# design.net
KiCad netlist of a schematic drawn in EasyEDA Pro
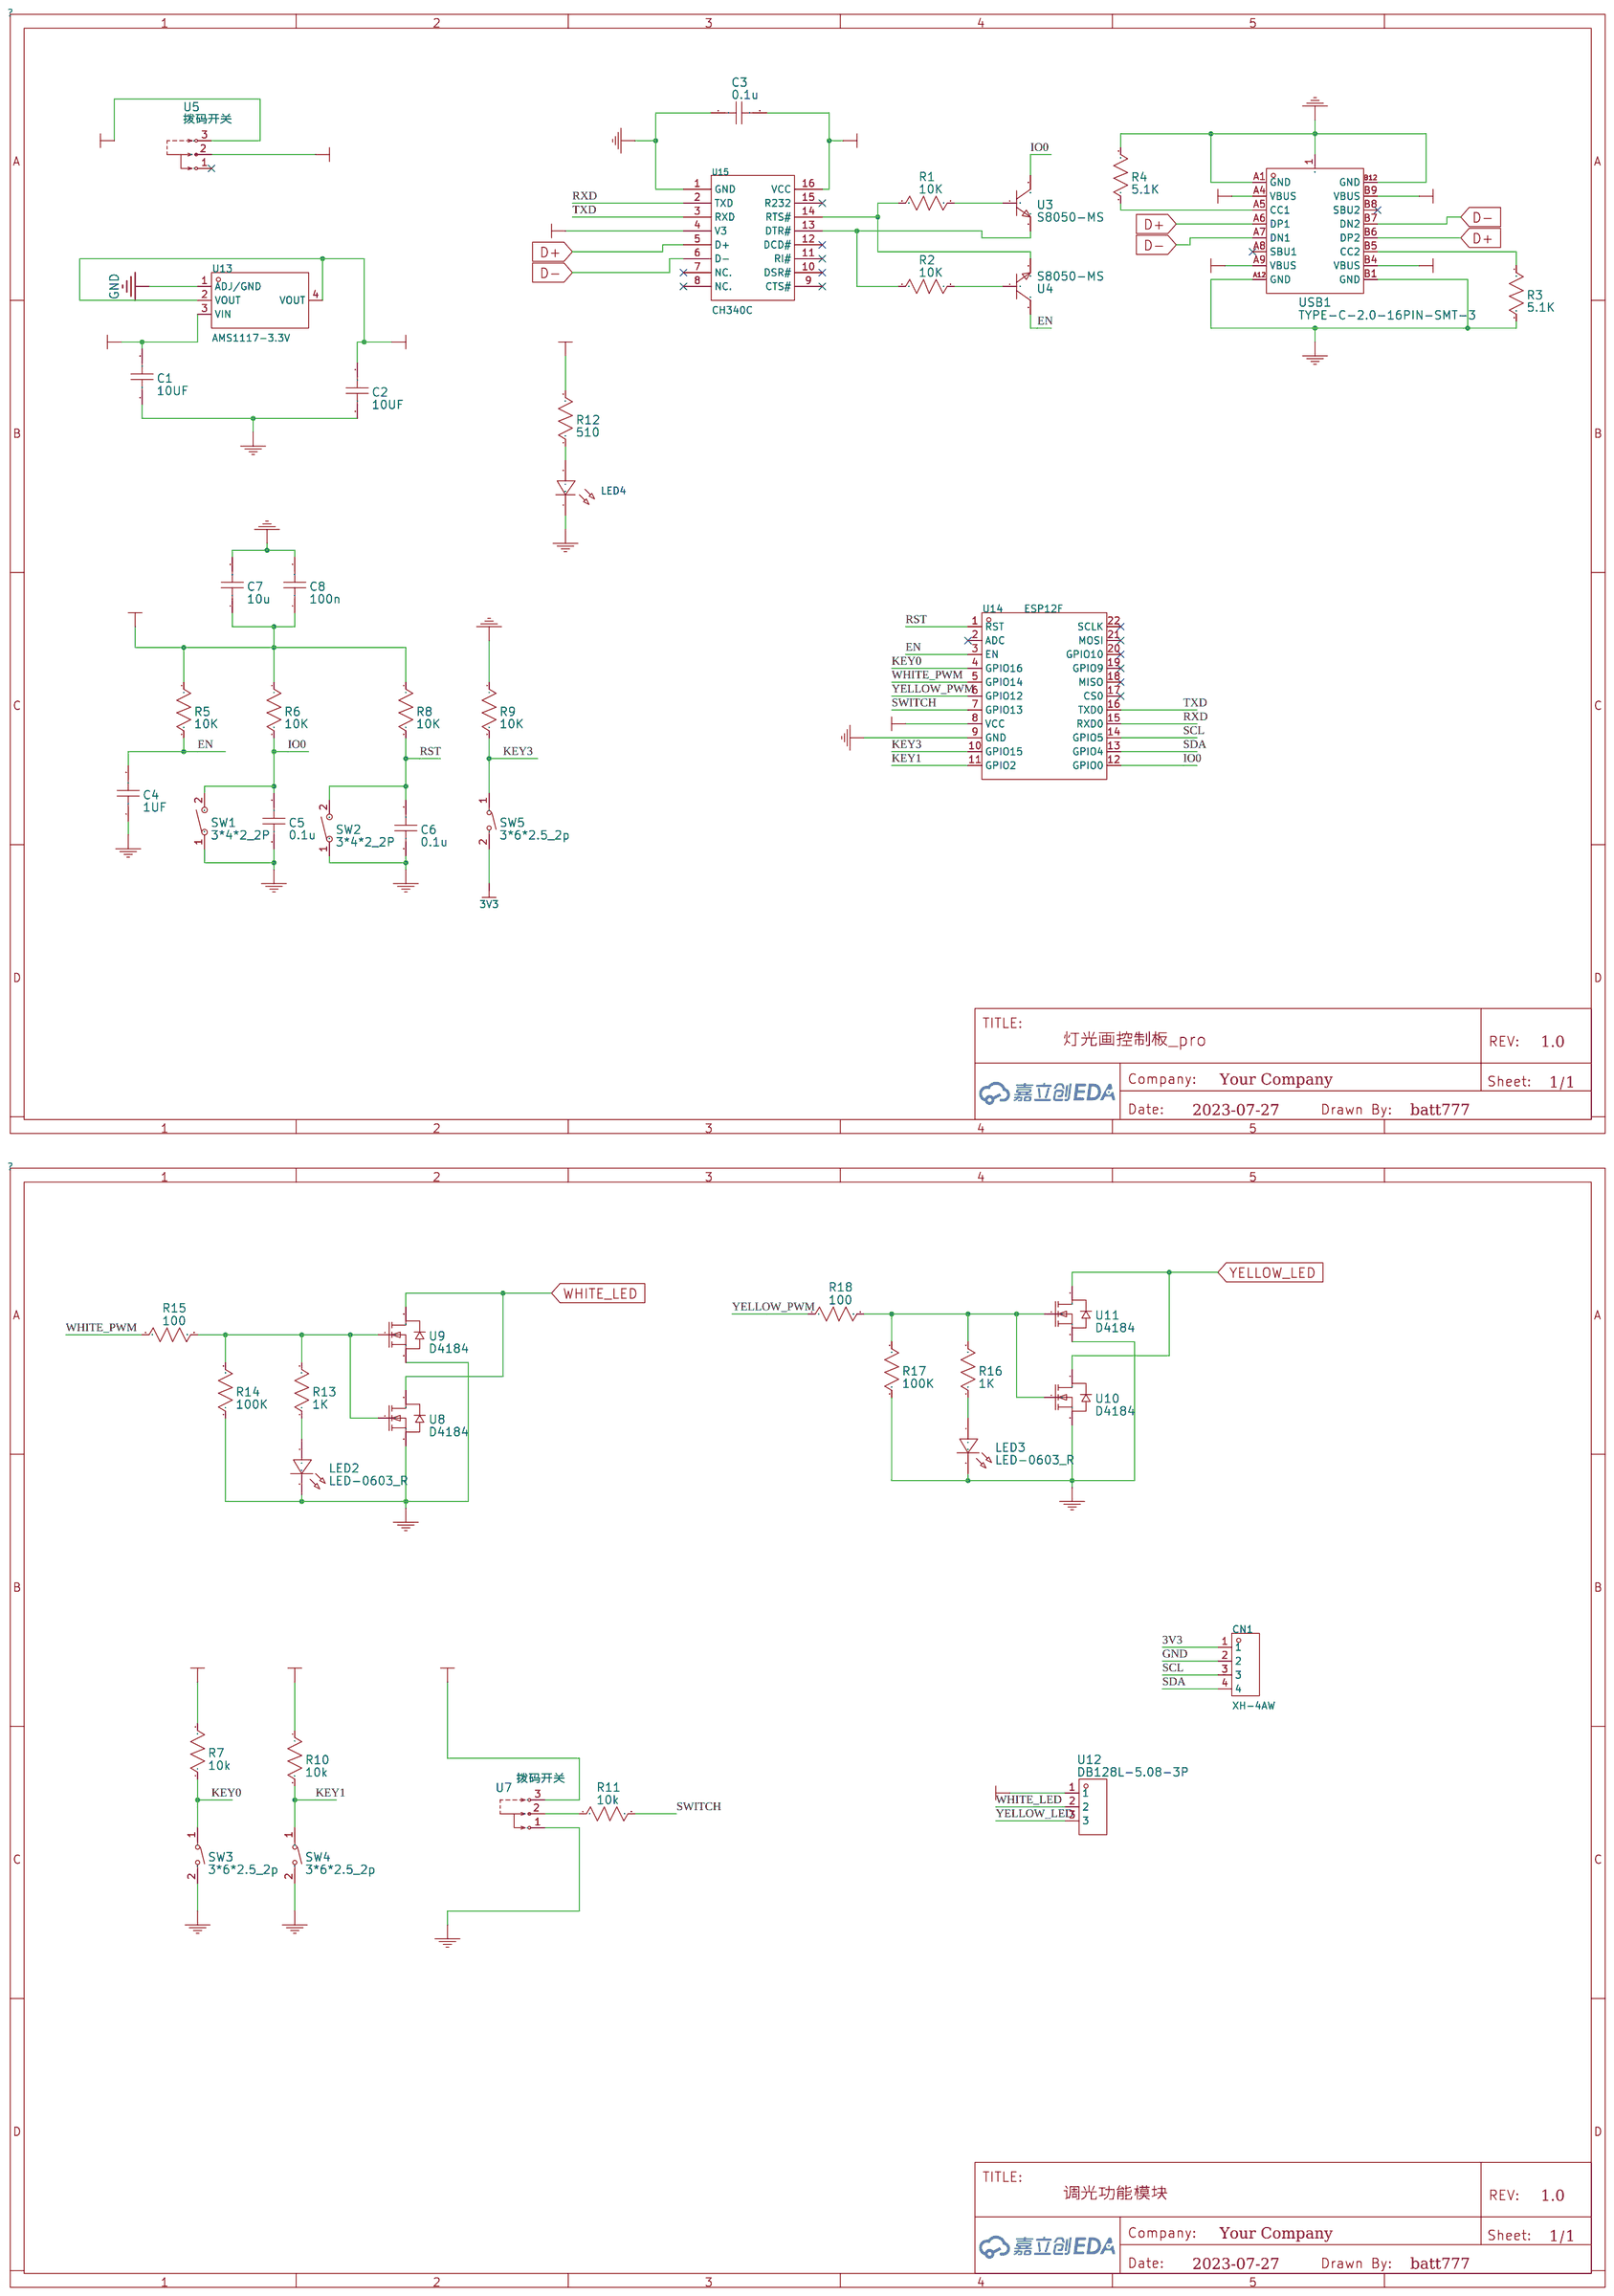
[diagram p0: schematic sheet]

(export (version "E")
  (design (tool "Eeschema 10.0.6"))
  (components
    (comp (ref "C1")
      (value "10UF")
      (footprint "easyedapro:C0603")
      (libsource (lib "easyedapro") (part "22UF"))
    )
    (comp (ref "C2")
      (value "10UF")
      (footprint "easyedapro:C0603")
      (libsource (lib "easyedapro") (part "22UF"))
    )
    (comp (ref "C3")
      (value "0.1u")
      (footprint "easyedapro:C0603")
      (libsource (lib "easyedapro") (part "0.1u"))
    )
    (comp (ref "C4") (value "1UF") (footprint "easyedapro:C0603") (libsource (lib "easyedapro") (part "1UF")))
    (comp (ref "C5")
      (value "0.1u")
      (footprint "easyedapro:C0603")
      (libsource (lib "easyedapro") (part "0.1u"))
    )
    (comp (ref "C6")
      (value "0.1u")
      (footprint "easyedapro:C0603")
      (libsource (lib "easyedapro") (part "0.1u"))
    )
    (comp (ref "C7") (value "10u") (footprint "easyedapro:C0603") (libsource (lib "easyedapro") (part "10u")))
    (comp (ref "C8")
      (value "100n")
      (footprint "easyedapro:C0603")
      (libsource (lib "easyedapro") (part "100n"))
    )
    (comp (ref "CN1")
      (value "XH-4AW")
      (footprint "easyedapro:CONN-TH_XH-4AW")
      (description "参考系列:XH;间距:2.54mm;插针结构:1x4P;排数:1;每排PIN数:4;行距:-;公母:公型插针;安装方式:弯插;额定电流:3A;工作温度范围:-25°C~+85°C;")
      (fields (field (name "Manufacturer") "HCTL(华灿天禄)"))
      (libsource (lib "easyedapro") (part "XH-4AW_C2908613"))
    )
    (comp (ref "LED2")
      (value "LED-0603_R")
      (footprint "easyedapro:LED0603_RED")
      (fields
        (field (name "Manufacturer Part") "19-217/R6C-AL1M2VY/3T")
        (field (name "Manufacturer") "EVERLIGHT(台湾亿光)")
      )
      (libsource (lib "easyedapro") (part "LED-0603_R"))
    )
    (comp (ref "LED3")
      (value "LED-0603_R")
      (footprint "easyedapro:LED0603_RED")
      (fields
        (field (name "Manufacturer Part") "19-217/R6C-AL1M2VY/3T")
        (field (name "Manufacturer") "EVERLIGHT(台湾亿光)")
      )
      (libsource (lib "easyedapro") (part "LED-0603_R"))
    )
    (comp (ref "LED4")
      (value "~")
      (footprint "easyedapro:LED_0603")
      (libsource (lib "easyedapro") (part "LED_B"))
    )
    (comp (ref "R1") (value "10K") (footprint "easyedapro:R0603") (libsource (lib "easyedapro") (part "10K")))
    (comp (ref "R2") (value "10K") (footprint "easyedapro:R0603") (libsource (lib "easyedapro") (part "10K")))
    (comp (ref "R3")
      (value "5.1K")
      (footprint "easyedapro:R0603")
      (libsource (lib "easyedapro") (part "5.1K"))
    )
    (comp (ref "R4")
      (value "5.1K")
      (footprint "easyedapro:R0603")
      (libsource (lib "easyedapro") (part "5.1K"))
    )
    (comp (ref "R5") (value "10K") (footprint "easyedapro:R0603") (libsource (lib "easyedapro") (part "10K")))
    (comp (ref "R6") (value "10K") (footprint "easyedapro:R0603") (libsource (lib "easyedapro") (part "10K")))
    (comp (ref "R7") (value "10k") (footprint "easyedapro:R0603") (libsource (lib "easyedapro") (part "10k")))
    (comp (ref "R8") (value "10K") (footprint "easyedapro:R0603") (libsource (lib "easyedapro") (part "10K")))
    (comp (ref "R9") (value "10K") (footprint "easyedapro:R0603") (libsource (lib "easyedapro") (part "10K")))
    (comp (ref "R10")
      (value "10k")
      (footprint "easyedapro:R0603")
      (libsource (lib "easyedapro") (part "10k"))
    )
    (comp (ref "R11")
      (value "10k")
      (footprint "easyedapro:R0603")
      (libsource (lib "easyedapro") (part "10k"))
    )
    (comp (ref "R12")
      (value "510")
      (footprint "easyedapro:R0603")
      (libsource (lib "easyedapro") (part "510"))
    )
    (comp (ref "R13") (value "1K") (footprint "easyedapro:R0603") (libsource (lib "easyedapro") (part "1K")))
    (comp (ref "R14")
      (value "100K")
      (footprint "easyedapro:R0603")
      (libsource (lib "easyedapro") (part "100K"))
    )
    (comp (ref "R15")
      (value "100")
      (footprint "easyedapro:R0603")
      (libsource (lib "easyedapro") (part "100"))
    )
    (comp (ref "R16") (value "1K") (footprint "easyedapro:R0603") (libsource (lib "easyedapro") (part "1K")))
    (comp (ref "R17")
      (value "100K")
      (footprint "easyedapro:R0603")
      (libsource (lib "easyedapro") (part "100K"))
    )
    (comp (ref "R18")
      (value "100")
      (footprint "easyedapro:R0603")
      (libsource (lib "easyedapro") (part "100"))
    )
    (comp (ref "SW1")
      (value "3*4*2_2P")
      (footprint "easyedapro:SW-SMD_L4.0-W2.9-LS5.0")
      (fields (field (name "Manufacturer") "SHOU HAN(首韩)"))
      (libsource (lib "easyedapro") (part "3*4*2_2P"))
    )
    (comp (ref "SW2")
      (value "3*4*2_2P")
      (footprint "easyedapro:SW-SMD_L4.0-W2.9-LS5.0")
      (fields (field (name "Manufacturer") "SHOU HAN(首韩)"))
      (libsource (lib "easyedapro") (part "3*4*2_2P"))
    )
    (comp (ref "SW3")
      (value "3*6*2.5_2p")
      (footprint "easyedapro:SW-SMD_L6.1-W3.5-LS8.0")
      (fields
        (field (name "Manufacturer Part") "GT-TC060A-H025-L1")
        (field (name "Manufacturer") "G-Switch(品赞)")
      )
      (libsource (lib "easyedapro") (part "3*6*2.5_2p"))
    )
    (comp (ref "SW4")
      (value "3*6*2.5_2p")
      (footprint "easyedapro:SW-SMD_L6.1-W3.5-LS8.0")
      (fields
        (field (name "Manufacturer Part") "GT-TC060A-H025-L1")
        (field (name "Manufacturer") "G-Switch(品赞)")
      )
      (libsource (lib "easyedapro") (part "3*6*2.5_2p"))
    )
    (comp (ref "SW5")
      (value "3*6*2.5_2p")
      (footprint "easyedapro:SW-SMD_L6.1-W3.5-LS8.0")
      (fields
        (field (name "Manufacturer Part") "GT-TC060A-H025-L1")
        (field (name "Manufacturer") "G-Switch(品赞)")
      )
      (libsource (lib "easyedapro") (part "3*6*2.5_2p"))
    )
    (comp (ref "U3")
      (value "S8050-MS")
      (footprint "easyedapro:SOT-23-3_L2.9-W1.3-P1.90-LS2.4-BR")
      (fields (field (name "Manufacturer") "MSKSEMI(美森科)"))
      (libsource (lib "easyedapro") (part "S8050-MS"))
    )
    (comp (ref "U4")
      (value "S8050-MS")
      (footprint "easyedapro:SOT-23-3_L2.9-W1.3-P1.90-LS2.4-BR")
      (fields (field (name "Manufacturer") "MSKSEMI(美森科)"))
      (libsource (lib "") (part "S8050-MS_1"))
    )
    (comp (ref "U5")
      (value "拨码开关")
      (footprint "easyedapro:SW-TH_SHOU-HAN_SS12D10G4")
      (fields (field (name "Manufacturer Part") "HX SS12D10G4") (field (name "Manufacturer") "hanxia(韩下)"))
      (libsource (lib "easyedapro") (part "拨码开关"))
    )
    (comp (ref "U7")
      (value "拨码开关")
      (footprint "easyedapro:SW-TH_SHOU-HAN_SS12D10G4")
      (fields (field (name "Manufacturer Part") "HX SS12D10G4") (field (name "Manufacturer") "hanxia(韩下)"))
      (libsource (lib "easyedapro") (part "拨码开关"))
    )
    (comp (ref "U8")
      (value "D4184")
      (footprint "easyedapro:TO-252-3_L6.6-W6.1-P4.57-LS9.9-BR-CW")
      (fields (field (name "Manufacturer") "TECH PUBLIC(台舟)"))
      (libsource (lib "easyedapro") (part "D4184"))
    )
    (comp (ref "U9")
      (value "D4184")
      (footprint "easyedapro:TO-252-3_L6.6-W6.1-P4.57-LS9.9-BR-CW")
      (fields (field (name "Manufacturer") "TECH PUBLIC(台舟)"))
      (libsource (lib "easyedapro") (part "D4184"))
    )
    (comp (ref "U10")
      (value "D4184")
      (footprint "easyedapro:TO-252-3_L6.6-W6.1-P4.57-LS9.9-BR-CW")
      (fields (field (name "Manufacturer") "TECH PUBLIC(台舟)"))
      (libsource (lib "easyedapro") (part "D4184"))
    )
    (comp (ref "U11")
      (value "D4184")
      (footprint "easyedapro:TO-252-3_L6.6-W6.1-P4.57-LS9.9-BR-CW")
      (fields (field (name "Manufacturer") "TECH PUBLIC(台舟)"))
      (libsource (lib "easyedapro") (part "D4184"))
    )
    (comp (ref "U12")
      (value "DB128L-5.08-3P")
      (footprint "easyedapro:CONN-TH_DB128L-5.08-3P")
      (fields
        (field (name "Manufacturer Part") "DB128L-5.08-3P-GN-S")
        (field (name "Manufacturer") "DIBO(地博电气)")
      )
      (libsource (lib "easyedapro") (part "DB128L-5.08-3P"))
    )
    (comp (ref "U13")
      (value "AMS1117-3.3V")
      (footprint "easyedapro:SOT-223-4_L6.5-W3.5-P2.30-LS7.0-BR")
      (fields (field (name "Manufacturer") "WPMtek(维攀微)"))
      (libsource (lib "easyedapro") (part "AMS1117-3.3V"))
    )
    (comp (ref "U14")
      (value "ESP12F")
      (footprint "easyedapro:WIFIM-SMD_ESP-12F-ESP8266MOD")
      (description "频率:2.4GHz;发射功率:16dBm;核心处理器:ESP8266;天线形式:PCB 板载天线;接收灵敏度:-90dBm;")
      (fields
        (field (name "Manufacturer Part") "ESP-12F(ESP8266MOD)")
        (field (name "Manufacturer") "Ai-Thinker(安信可)")
      )
      (libsource (lib "easyedapro") (part "ESP-12F(ESP8266MOD)"))
    )
    (comp (ref "U15")
      (value "CH340C")
      (footprint "easyedapro:SOP-16_L10.0-W3.9-P1.27-LS6.0-BL")
      (description "应用功能:收发器;接口协议:USB 2.0;数据速率:2Mbps;")
      (fields (field (name "Manufacturer") "WCH(南京沁恒)"))
      (libsource (lib "easyedapro") (part "CH340C"))
    )
    (comp (ref "USB1")
      (value "TYPE-C-2.0-16PIN-SMT-3")
      (footprint "easyedapro:TYPE-C-SMD_TYPE-CF3.1")
      (fields (field (name "Manufacturer") "CIKI(皓富)"))
      (libsource (lib "easyedapro") (part "TYPE-C-2.0-16PIN-SMT-3"))
    )
  )
  (nets
    (net (code "1") (name "+5V") (class "Default")
      (node (ref "C1") (pin "2") (pinfunction "2_2") (pintype "input"))
      (node (ref "U12") (pin "1") (pinfunction "1_1") (pintype "input"))
      (node (ref "U13") (pin "3") (pinfunction "VIN_3") (pintype "input"))
      (node (ref "U5") (pin "2") (pinfunction "2_2") (pintype "input"))
    )
    (net (code "2") (name "/EN") (class "Default")
      (node (ref "C4") (pin "2") (pinfunction "2_2") (pintype "input"))
      (node (ref "R5") (pin "2") (pinfunction "2_2") (pintype "input"))
      (node (ref "U14") (pin "3") (pinfunction "EN_3") (pintype "input"))
      (node (ref "U4") (pin "3") (pinfunction "C_3") (pintype "input"))
    )
    (net (code "3") (name "/IO0") (class "Default")
      (node (ref "C5") (pin "2") (pinfunction "2_2") (pintype "input"))
      (node (ref "R6") (pin "2") (pinfunction "2_2") (pintype "input"))
      (node (ref "SW1") (pin "2") (pinfunction "2_2") (pintype "input"))
      (node (ref "U14") (pin "12") (pinfunction "GPIO0_12") (pintype "input"))
      (node (ref "U3") (pin "3") (pinfunction "C_3") (pintype "input"))
    )
    (net (code "4") (name "/KEY0") (class "Default")
      (node (ref "R7") (pin "1") (pinfunction "1_1") (pintype "input"))
      (node (ref "SW3") (pin "1") (pinfunction "1_1") (pintype "input"))
      (node (ref "U14") (pin "4") (pinfunction "GPIO16_4") (pintype "input"))
    )
    (net (code "5") (name "/KEY1") (class "Default")
      (node (ref "R10") (pin "2") (pinfunction "2_2") (pintype "input"))
      (node (ref "SW4") (pin "1") (pinfunction "1_1") (pintype "input"))
      (node (ref "U14") (pin "11") (pinfunction "GPIO2_11") (pintype "input"))
    )
    (net (code "6") (name "/KEY3") (class "Default")
      (node (ref "R9") (pin "2") (pinfunction "2_2") (pintype "input"))
      (node (ref "SW5") (pin "1") (pinfunction "1_1") (pintype "input"))
      (node (ref "U14") (pin "10") (pinfunction "GPIO15_10") (pintype "input"))
    )
    (net (code "7") (name "/RST") (class "Default")
      (node (ref "C6") (pin "2") (pinfunction "2_2") (pintype "input"))
      (node (ref "R8") (pin "2") (pinfunction "2_2") (pintype "input"))
      (node (ref "SW2") (pin "2") (pinfunction "2_2") (pintype "input"))
      (node (ref "U14") (pin "1") (pinfunction "RST_1") (pintype "input"))
    )
    (net (code "8") (name "/RXD") (class "Default")
      (node (ref "U14") (pin "15") (pinfunction "RXD0_15") (pintype "input"))
      (node (ref "U15") (pin "2") (pinfunction "TXD_2") (pintype "input"))
    )
    (net (code "9") (name "/SCL") (class "Default")
      (node (ref "CN1") (pin "3") (pinfunction "3_3") (pintype "input"))
      (node (ref "U14") (pin "14") (pinfunction "GPIO5_14") (pintype "input"))
    )
    (net (code "10") (name "/SDA") (class "Default")
      (node (ref "CN1") (pin "4") (pinfunction "4_4") (pintype "input"))
      (node (ref "U14") (pin "13") (pinfunction "GPIO4_13") (pintype "input"))
    )
    (net (code "11") (name "/SWITCH") (class "Default")
      (node (ref "R11") (pin "2") (pinfunction "2_2") (pintype "input"))
      (node (ref "U14") (pin "7") (pinfunction "GPIO13_7") (pintype "input"))
    )
    (net (code "12") (name "/TXD") (class "Default")
      (node (ref "U14") (pin "16") (pinfunction "TXD0_16") (pintype "input"))
      (node (ref "U15") (pin "3") (pinfunction "RXD_3") (pintype "input"))
    )
    (net (code "13") (name "/WHITE_PWM") (class "Default")
      (node (ref "R15") (pin "1") (pinfunction "1_1") (pintype "input"))
      (node (ref "U14") (pin "5") (pinfunction "GPIO14_5") (pintype "input"))
    )
    (net (code "14") (name "/YELLOW_PWM") (class "Default")
      (node (ref "R18") (pin "1") (pinfunction "1_1") (pintype "input"))
      (node (ref "U14") (pin "6") (pinfunction "GPIO12_6") (pintype "input"))
    )
    (net (code "15") (name "3V3") (class "Default")
      (node (ref "C2") (pin "2") (pinfunction "2_2") (pintype "input"))
      (node (ref "C3") (pin "2") (pinfunction "2_2") (pintype "input"))
      (node (ref "C7") (pin "1") (pinfunction "1_1") (pintype "input"))
      (node (ref "C8") (pin "1") (pinfunction "1_1") (pintype "input"))
      (node (ref "CN1") (pin "1") (pinfunction "1_1") (pintype "input"))
      (node (ref "R10") (pin "1") (pinfunction "1_1") (pintype "input"))
      (node (ref "R12") (pin "2") (pinfunction "2_2") (pintype "input"))
      (node (ref "R5") (pin "1") (pinfunction "1_1") (pintype "input"))
      (node (ref "R6") (pin "1") (pinfunction "1_1") (pintype "input"))
      (node (ref "R7") (pin "2") (pinfunction "2_2") (pintype "input"))
      (node (ref "R8") (pin "1") (pinfunction "1_1") (pintype "input"))
      (node (ref "SW5") (pin "2") (pinfunction "2_2") (pintype "input"))
      (node (ref "U13") (pin "2") (pinfunction "VOUT_2") (pintype "input"))
      (node (ref "U13") (pin "4") (pinfunction "VOUT_4") (pintype "input"))
      (node (ref "U14") (pin "8") (pinfunction "VCC_8") (pintype "input"))
      (node (ref "U15") (pin "16") (pinfunction "VCC_16") (pintype "input"))
      (node (ref "U15") (pin "4") (pinfunction "V3_4") (pintype "input"))
      (node (ref "U7") (pin "3") (pinfunction "3_3") (pintype "input"))
    )
    (net (code "16") (name "5V_OUT") (class "Default")
      (node (ref "U5") (pin "3") (pinfunction "3_3") (pintype "input"))
      (node (ref "USB1") (pin "A4") (pinfunction "VBUS_A4") (pintype "input"))
      (node (ref "USB1") (pin "A9") (pinfunction "VBUS_A9") (pintype "input"))
      (node (ref "USB1") (pin "B4") (pinfunction "VBUS_B4") (pintype "input"))
      (node (ref "USB1") (pin "B9") (pinfunction "VBUS_B9") (pintype "input"))
    )
    (net (code "17") (name "D+") (class "Default")
      (node (ref "U15") (pin "5") (pinfunction "D+_5") (pintype "input"))
      (node (ref "USB1") (pin "A6") (pinfunction "DP1_A6") (pintype "input"))
      (node (ref "USB1") (pin "B6") (pinfunction "DP2_B6") (pintype "input"))
    )
    (net (code "18") (name "D-") (class "Default")
      (node (ref "U15") (pin "6") (pinfunction "D-_6") (pintype "input"))
      (node (ref "USB1") (pin "A7") (pinfunction "DN1_A7") (pintype "input"))
      (node (ref "USB1") (pin "B7") (pinfunction "DN2_B7") (pintype "input"))
    )
    (net (code "19") (name "GND") (class "Default")
      (node (ref "C1") (pin "1") (pinfunction "1_1") (pintype "input"))
      (node (ref "C2") (pin "1") (pinfunction "1_1") (pintype "input"))
      (node (ref "C3") (pin "1") (pinfunction "1_1") (pintype "input"))
      (node (ref "C4") (pin "1") (pinfunction "1_1") (pintype "input"))
      (node (ref "C5") (pin "1") (pinfunction "1_1") (pintype "input"))
      (node (ref "C6") (pin "1") (pinfunction "1_1") (pintype "input"))
      (node (ref "C7") (pin "2") (pinfunction "2_2") (pintype "input"))
      (node (ref "C8") (pin "2") (pinfunction "2_2") (pintype "input"))
      (node (ref "CN1") (pin "2") (pinfunction "2_2") (pintype "input"))
      (node (ref "LED2") (pin "2") (pinfunction "2_2") (pintype "input"))
      (node (ref "LED3") (pin "2") (pinfunction "2_2") (pintype "input"))
      (node (ref "LED4") (pin "1") (pinfunction "C_1") (pintype "input"))
      (node (ref "R14") (pin "1") (pinfunction "1_1") (pintype "input"))
      (node (ref "R17") (pin "1") (pinfunction "1_1") (pintype "input"))
      (node (ref "R3") (pin "1") (pinfunction "1_1") (pintype "input"))
      (node (ref "R4") (pin "2") (pinfunction "2_2") (pintype "input"))
      (node (ref "R9") (pin "1") (pinfunction "1_1") (pintype "input"))
      (node (ref "SW1") (pin "1") (pinfunction "1_1") (pintype "input"))
      (node (ref "SW2") (pin "1") (pinfunction "1_1") (pintype "input"))
      (node (ref "SW3") (pin "2") (pinfunction "2_2") (pintype "input"))
      (node (ref "SW4") (pin "2") (pinfunction "2_2") (pintype "input"))
      (node (ref "U10") (pin "3") (pinfunction "S_3") (pintype "input"))
      (node (ref "U11") (pin "3") (pinfunction "S_3") (pintype "input"))
      (node (ref "U13") (pin "1") (pinfunction "ADJ/GND_1") (pintype "input"))
      (node (ref "U14") (pin "9") (pinfunction "GND_9") (pintype "input"))
      (node (ref "U15") (pin "1") (pinfunction "GND_1") (pintype "input"))
      (node (ref "U7") (pin "1") (pinfunction "1_1") (pintype "input"))
      (node (ref "U8") (pin "3") (pinfunction "S_3") (pintype "input"))
      (node (ref "U9") (pin "3") (pinfunction "S_3") (pintype "input"))
      (node (ref "USB1") (pin "1") (pinfunction "EH_1") (pintype "input"))
      (node (ref "USB1") (pin "A1") (pinfunction "GND_A1") (pintype "input"))
      (node (ref "USB1") (pin "A12") (pinfunction "GND_A12") (pintype "input"))
      (node (ref "USB1") (pin "B1") (pinfunction "GND_B1") (pintype "input"))
      (node (ref "USB1") (pin "B12") (pinfunction "GND_B12") (pintype "input"))
    )
    (net (code "20") (name "Net-(LED2-Pad1)") (class "Default")
      (node (ref "LED2") (pin "1") (pinfunction "1_1") (pintype "input"))
      (node (ref "R13") (pin "1") (pinfunction "1_1") (pintype "input"))
    )
    (net (code "21") (name "Net-(LED3-Pad1)") (class "Default")
      (node (ref "LED3") (pin "1") (pinfunction "1_1") (pintype "input"))
      (node (ref "R16") (pin "1") (pinfunction "1_1") (pintype "input"))
    )
    (net (code "22") (name "Net-(LED4-A)") (class "Default")
      (node (ref "LED4") (pin "2") (pinfunction "A_2") (pintype "input"))
      (node (ref "R12") (pin "1") (pinfunction "1_1") (pintype "input"))
    )
    (net (code "23") (name "Net-(R11-Pad1)") (class "Default")
      (node (ref "R11") (pin "1") (pinfunction "1_1") (pintype "input"))
      (node (ref "U7") (pin "2") (pinfunction "2_2") (pintype "input"))
    )
    (net (code "24") (name "Net-(U3-B)") (class "Default")
      (node (ref "R1") (pin "2") (pinfunction "2_2") (pintype "input"))
      (node (ref "U3") (pin "1") (pinfunction "B_1") (pintype "input"))
    )
    (net (code "25") (name "Net-(U4-B)") (class "Default")
      (node (ref "R2") (pin "2") (pinfunction "2_2") (pintype "input"))
      (node (ref "U4") (pin "1") (pinfunction "B_1") (pintype "input"))
    )
    (net (code "26") (name "Net-(U8-G)") (class "Default")
      (node (ref "R13") (pin "2") (pinfunction "2_2") (pintype "input"))
      (node (ref "R14") (pin "2") (pinfunction "2_2") (pintype "input"))
      (node (ref "R15") (pin "2") (pinfunction "2_2") (pintype "input"))
      (node (ref "U8") (pin "1") (pinfunction "G_1") (pintype "input"))
      (node (ref "U9") (pin "1") (pinfunction "G_1") (pintype "input"))
    )
    (net (code "27") (name "Net-(U10-G)") (class "Default")
      (node (ref "R16") (pin "2") (pinfunction "2_2") (pintype "input"))
      (node (ref "R17") (pin "2") (pinfunction "2_2") (pintype "input"))
      (node (ref "R18") (pin "2") (pinfunction "2_2") (pintype "input"))
      (node (ref "U10") (pin "1") (pinfunction "G_1") (pintype "input"))
      (node (ref "U11") (pin "1") (pinfunction "G_1") (pintype "input"))
    )
    (net (code "28") (name "Net-(U15-DTR#)") (class "Default")
      (node (ref "R2") (pin "1") (pinfunction "1_1") (pintype "input"))
      (node (ref "U15") (pin "13") (pinfunction "DTR#_13") (pintype "input"))
      (node (ref "U3") (pin "2") (pinfunction "E_2") (pintype "input"))
    )
    (net (code "29") (name "Net-(U15-RTS#)") (class "Default")
      (node (ref "R1") (pin "1") (pinfunction "1_1") (pintype "input"))
      (node (ref "U15") (pin "14") (pinfunction "RTS#_14") (pintype "input"))
      (node (ref "U4") (pin "2") (pinfunction "E_2") (pintype "input"))
    )
    (net (code "30") (name "Net-(USB1-CC1)") (class "Default")
      (node (ref "R4") (pin "1") (pinfunction "1_1") (pintype "input"))
      (node (ref "USB1") (pin "A5") (pinfunction "CC1_A5") (pintype "input"))
    )
    (net (code "31") (name "Net-(USB1-CC2)") (class "Default")
      (node (ref "R3") (pin "2") (pinfunction "2_2") (pintype "input"))
      (node (ref "USB1") (pin "B5") (pinfunction "CC2_B5") (pintype "input"))
    )
    (net (code "32") (name "WHITE_LED") (class "Default")
      (node (ref "U12") (pin "2") (pinfunction "2_2") (pintype "input"))
      (node (ref "U8") (pin "2") (pinfunction "D_2") (pintype "input"))
      (node (ref "U9") (pin "2") (pinfunction "D_2") (pintype "input"))
    )
    (net (code "33") (name "YELLOW_LED") (class "Default")
      (node (ref "U10") (pin "2") (pinfunction "D_2") (pintype "input"))
      (node (ref "U11") (pin "2") (pinfunction "D_2") (pintype "input"))
      (node (ref "U12") (pin "3") (pinfunction "3_3") (pintype "input"))
    )
    (net (code "34") (name "unconnected-(U5-Pad1)") (class "Default")
      (node (ref "U5") (pin "1") (pinfunction "1_1") (pintype "input+no_connect"))
    )
    (net (code "35") (name "unconnected-(U14-ADC-Pad2)") (class "Default")
      (node (ref "U14") (pin "2") (pinfunction "ADC_2") (pintype "input+no_connect"))
    )
    (net (code "36") (name "unconnected-(U14-CS0-Pad17)") (class "Default")
      (node (ref "U14") (pin "17") (pinfunction "CS0_17") (pintype "input+no_connect"))
    )
    (net (code "37") (name "unconnected-(U14-GPIO9-Pad19)") (class "Default")
      (node (ref "U14") (pin "19") (pinfunction "GPIO9_19") (pintype "input+no_connect"))
    )
    (net (code "38") (name "unconnected-(U14-GPIO10-Pad20)") (class "Default")
      (node (ref "U14") (pin "20") (pinfunction "GPIO10_20") (pintype "input+no_connect"))
    )
    (net (code "39") (name "unconnected-(U14-MISO-Pad18)") (class "Default")
      (node (ref "U14") (pin "18") (pinfunction "MISO_18") (pintype "input+no_connect"))
    )
    (net (code "40") (name "unconnected-(U14-MOSI-Pad21)") (class "Default")
      (node (ref "U14") (pin "21") (pinfunction "MOSI_21") (pintype "input+no_connect"))
    )
    (net (code "41") (name "unconnected-(U14-SCLK-Pad22)") (class "Default")
      (node (ref "U14") (pin "22") (pinfunction "SCLK_22") (pintype "input+no_connect"))
    )
    (net (code "42") (name "unconnected-(U15-CTS#-Pad9)") (class "Default")
      (node (ref "U15") (pin "9") (pinfunction "CTS#_9") (pintype "input+no_connect"))
    )
    (net (code "43") (name "unconnected-(U15-DCD#-Pad12)") (class "Default")
      (node (ref "U15") (pin "12") (pinfunction "DCD#_12") (pintype "input+no_connect"))
    )
    (net (code "44") (name "unconnected-(U15-DSR#-Pad10)") (class "Default")
      (node (ref "U15") (pin "10") (pinfunction "DSR#_10") (pintype "input+no_connect"))
    )
    (net (code "45") (name "unconnected-(U15-NC.-Pad7)") (class "Default")
      (node (ref "U15") (pin "7") (pinfunction "NC._7") (pintype "input+no_connect"))
    )
    (net (code "46") (name "unconnected-(U15-NC.-Pad8)") (class "Default")
      (node (ref "U15") (pin "8") (pinfunction "NC._8") (pintype "input+no_connect"))
    )
    (net (code "47") (name "unconnected-(U15-R232-Pad15)") (class "Default")
      (node (ref "U15") (pin "15") (pinfunction "R232_15") (pintype "input+no_connect"))
    )
    (net (code "48") (name "unconnected-(U15-RI#-Pad11)") (class "Default")
      (node (ref "U15") (pin "11") (pinfunction "RI#_11") (pintype "input+no_connect"))
    )
    (net (code "49") (name "unconnected-(USB1-SBU1-PadA8)") (class "Default")
      (node (ref "USB1") (pin "A8") (pinfunction "SBU1_A8") (pintype "input+no_connect"))
    )
    (net (code "50") (name "unconnected-(USB1-SBU2-PadB8)") (class "Default")
      (node (ref "USB1") (pin "B8") (pinfunction "SBU2_B8") (pintype "input+no_connect"))
    )
  )
)
